# FOC_Driver.net
KiCad netlist of a schematic drawn in Altium Designer
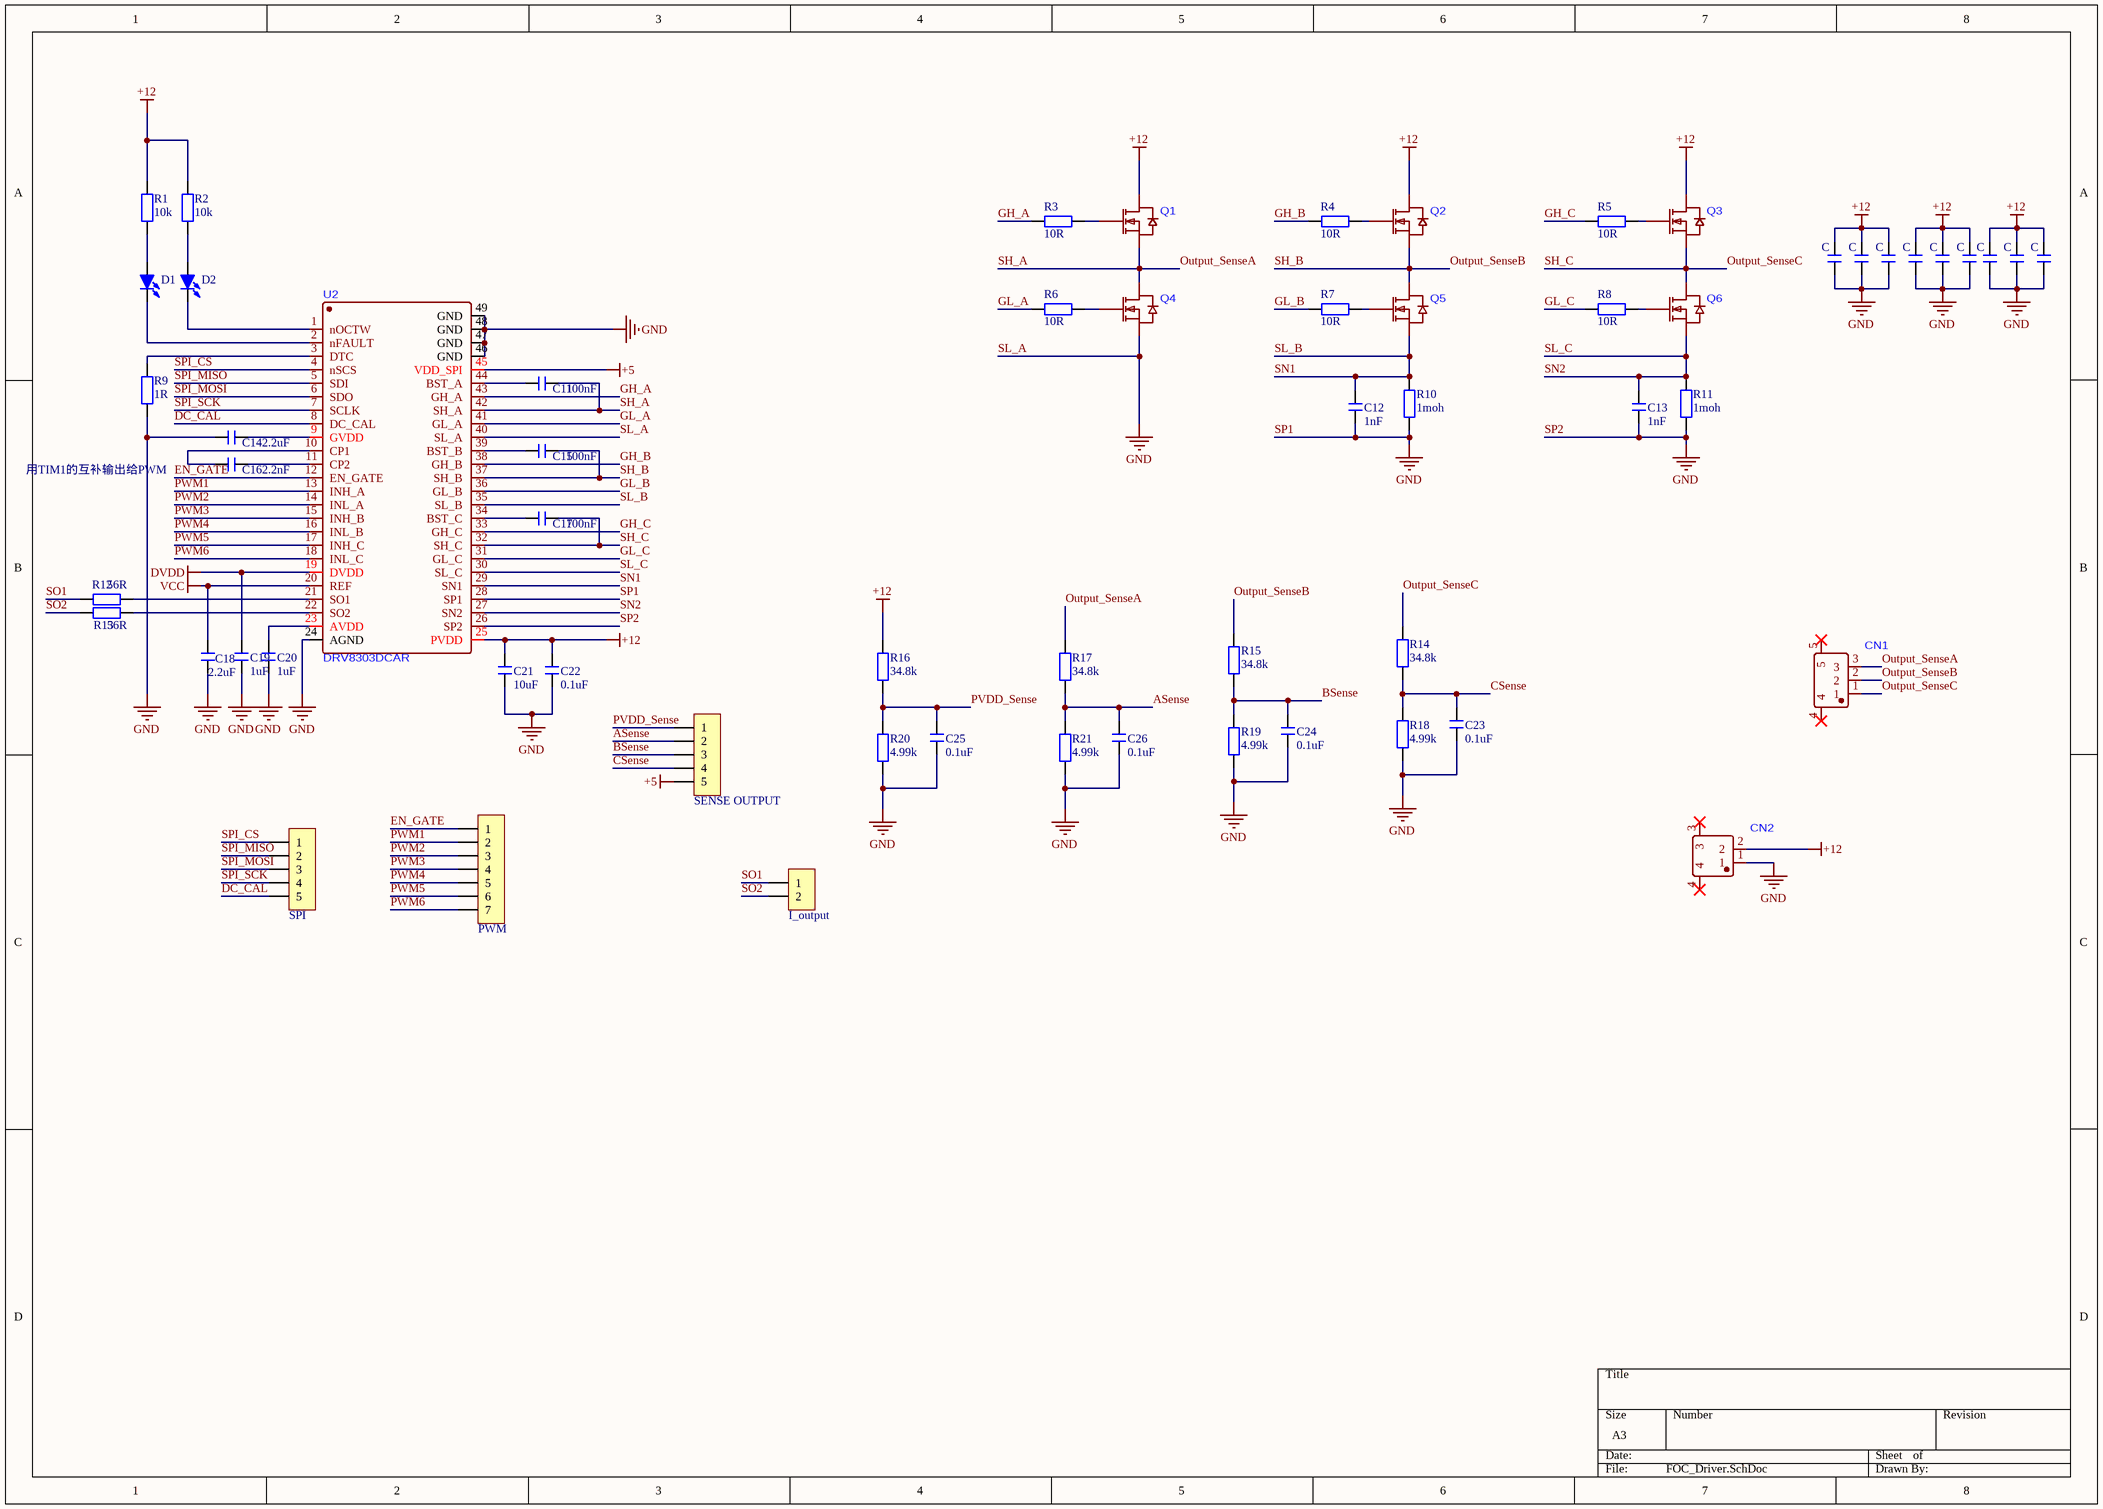
[diagram p0: FOC_Driver.SchDoc]

(export (version "E")
  (design (tool "Eeschema 10.0.6"))
  (components
    (comp (ref "C2")
      (value "C")
      (footprint "C 0805_M")
      (description "无极性贴片电容")
      (fields (field (name "版权归属") "电协硬件组"))
      (libsource (lib "3.1   - 电阻-电容-电感") (part "C"))
    )
    (comp (ref "C3")
      (value "C")
      (footprint "C 0805_M")
      (description "无极性贴片电容")
      (fields (field (name "版权归属") "电协硬件组"))
      (libsource (lib "3.1   - 电阻-电容-电感") (part "C"))
    )
    (comp (ref "C4")
      (value "C")
      (footprint "C 0805_M")
      (description "无极性贴片电容")
      (fields (field (name "版权归属") "电协硬件组"))
      (libsource (lib "3.1   - 电阻-电容-电感") (part "C"))
    )
    (comp (ref "C5")
      (value "C")
      (footprint "C 0805_M")
      (description "无极性贴片电容")
      (fields (field (name "版权归属") "电协硬件组"))
      (libsource (lib "3.1   - 电阻-电容-电感") (part "C"))
    )
    (comp (ref "C6")
      (value "C")
      (footprint "C 0805_M")
      (description "无极性贴片电容")
      (fields (field (name "版权归属") "电协硬件组"))
      (libsource (lib "3.1   - 电阻-电容-电感") (part "C"))
    )
    (comp (ref "C7")
      (value "C")
      (footprint "C 0805_M")
      (description "无极性贴片电容")
      (fields (field (name "版权归属") "电协硬件组"))
      (libsource (lib "3.1   - 电阻-电容-电感") (part "C"))
    )
    (comp (ref "C8")
      (value "C")
      (footprint "C 0805_M")
      (description "无极性贴片电容")
      (fields (field (name "版权归属") "电协硬件组"))
      (libsource (lib "3.1   - 电阻-电容-电感") (part "C"))
    )
    (comp (ref "C9")
      (value "C")
      (footprint "C 0805_M")
      (description "无极性贴片电容")
      (fields (field (name "版权归属") "电协硬件组"))
      (libsource (lib "3.1   - 电阻-电容-电感") (part "C"))
    )
    (comp (ref "C10")
      (value "C")
      (footprint "C 0805_M")
      (description "无极性贴片电容")
      (fields (field (name "版权归属") "电协硬件组"))
      (libsource (lib "3.1   - 电阻-电容-电感") (part "C"))
    )
    (comp (ref "C11")
      (value "100nF")
      (footprint "C 0603_M")
      (description "无极性贴片电容")
      (fields (field (name "版权归属") "电协硬件组"))
      (libsource (lib "3.1   - 电阻-电容-电感") (part "C"))
    )
    (comp (ref "C12")
      (value "1nF")
      (footprint "C 0603_M")
      (description "无极性贴片电容")
      (fields (field (name "版权归属") "电协硬件组"))
      (libsource (lib "3.1   - 电阻-电容-电感") (part "C"))
    )
    (comp (ref "C13")
      (value "1nF")
      (footprint "C 0603_M")
      (description "无极性贴片电容")
      (fields (field (name "版权归属") "电协硬件组"))
      (libsource (lib "3.1   - 电阻-电容-电感") (part "C"))
    )
    (comp (ref "C14")
      (value "2.2uF")
      (footprint "C 0603_M")
      (description "无极性贴片电容")
      (fields (field (name "版权归属") "电协硬件组"))
      (libsource (lib "3.1   - 电阻-电容-电感") (part "C"))
    )
    (comp (ref "C15")
      (value "100nF")
      (footprint "C 0603_M")
      (description "无极性贴片电容")
      (fields (field (name "版权归属") "电协硬件组"))
      (libsource (lib "3.1   - 电阻-电容-电感") (part "C"))
    )
    (comp (ref "C16")
      (value "2.2nF")
      (footprint "C 0603_M")
      (description "无极性贴片电容")
      (fields (field (name "版权归属") "电协硬件组"))
      (libsource (lib "3.1   - 电阻-电容-电感") (part "C"))
    )
    (comp (ref "C17")
      (value "100nF")
      (footprint "C 0603_M")
      (description "无极性贴片电容")
      (fields (field (name "版权归属") "电协硬件组"))
      (libsource (lib "3.1   - 电阻-电容-电感") (part "C"))
    )
    (comp (ref "C18")
      (value "2.2uF")
      (footprint "C 0603_M")
      (description "无极性贴片电容")
      (fields (field (name "版权归属") "电协硬件组"))
      (libsource (lib "3.1   - 电阻-电容-电感") (part "C"))
    )
    (comp (ref "C19")
      (value "1uF")
      (footprint "C 0603_M")
      (description "无极性贴片电容")
      (fields (field (name "版权归属") "电协硬件组"))
      (libsource (lib "3.1   - 电阻-电容-电感") (part "C"))
    )
    (comp (ref "C20")
      (value "1uF")
      (footprint "C 0603_M")
      (description "无极性贴片电容")
      (fields (field (name "版权归属") "电协硬件组"))
      (libsource (lib "3.1   - 电阻-电容-电感") (part "C"))
    )
    (comp (ref "C21")
      (value "10uF")
      (footprint "C 0603_M")
      (description "无极性贴片电容")
      (fields (field (name "版权归属") "电协硬件组"))
      (libsource (lib "3.1   - 电阻-电容-电感") (part "C"))
    )
    (comp (ref "C22")
      (value "0.1uF")
      (footprint "C 0603_M")
      (description "无极性贴片电容")
      (fields (field (name "版权归属") "电协硬件组"))
      (libsource (lib "3.1   - 电阻-电容-电感") (part "C"))
    )
    (comp (ref "C23")
      (value "0.1uF")
      (footprint "C 0603_M")
      (description "无极性贴片电容")
      (fields (field (name "版权归属") "电协硬件组"))
      (libsource (lib "3.1   - 电阻-电容-电感") (part "C"))
    )
    (comp (ref "C24")
      (value "0.1uF")
      (footprint "C 0603_M")
      (description "无极性贴片电容")
      (fields (field (name "版权归属") "电协硬件组"))
      (libsource (lib "3.1   - 电阻-电容-电感") (part "C"))
    )
    (comp (ref "C25")
      (value "0.1uF")
      (footprint "C 0603_M")
      (description "无极性贴片电容")
      (fields (field (name "版权归属") "电协硬件组"))
      (libsource (lib "3.1   - 电阻-电容-电感") (part "C"))
    )
    (comp (ref "C26")
      (value "0.1uF")
      (footprint "C 0603_M")
      (description "无极性贴片电容")
      (fields (field (name "版权归属") "电协硬件组"))
      (libsource (lib "3.1   - 电阻-电容-电感") (part "C"))
    )
    (comp (ref "CN1")
      (value "MR30PW-F")
      (footprint "CONN-TH_MR30PW-F")
      (libsource (lib "DRV8303") (part "MR30PW-F"))
    )
    (comp (ref "CN2")
      (value "XT30PW-M")
      (footprint "CONN-TH_XT30PW-M")
      (libsource (lib "主控") (part "XT30PW-M"))
    )
    (comp (ref "D1")
      (value "LED-SMD")
      (footprint "LED 0603G")
      (description "贴片LED")
      (fields (field (name "版权归属") "电协硬件组"))
      (libsource (lib "9.1   - LED") (part "LED-SMD"))
    )
    (comp (ref "D2")
      (value "LED-SMD")
      (footprint "LED 0603G")
      (description "贴片LED")
      (fields (field (name "版权归属") "电协硬件组"))
      (libsource (lib "9.1   - LED") (part "LED-SMD"))
    )
    (comp (ref "I_output")
      (value "HDR-1X2")
      (footprint "HDR2.54-LI-2P")
      (description "2P接插件")
      (fields (field (name "版权归属") "源创客"))
      (libsource (lib "4.5   - 接插件-脚距2.54") (part "Header 2"))
    )
    (comp (ref "PWM")
      (value "HDR-1X7")
      (footprint "HDR2.54-LI-7P")
      (description "7P接插件")
      (fields (field (name "版权归属") "源创客"))
      (libsource (lib "4.5   - 接插件-脚距2.54") (part "Header 7"))
    )
    (comp (ref "Q1")
      (value "IRLR7843TRPBF")
      (footprint "TO-252-2_L6.5-W6.1-P4.58-LS10.0-TR")
      (libsource (lib "驱动") (part "IRLR7843TRPBF"))
    )
    (comp (ref "Q2")
      (value "IRLR7843TRPBF")
      (footprint "TO-252-2_L6.5-W6.1-P4.58-LS10.0-TR")
      (libsource (lib "驱动") (part "IRLR7843TRPBF"))
    )
    (comp (ref "Q3")
      (value "IRLR7843TRPBF")
      (footprint "TO-252-2_L6.5-W6.1-P4.58-LS10.0-TR")
      (libsource (lib "驱动") (part "IRLR7843TRPBF"))
    )
    (comp (ref "Q4")
      (value "IRLR7843TRPBF")
      (footprint "TO-252-2_L6.5-W6.1-P4.58-LS10.0-TR")
      (libsource (lib "驱动") (part "IRLR7843TRPBF"))
    )
    (comp (ref "Q5")
      (value "IRLR7843TRPBF")
      (footprint "TO-252-2_L6.5-W6.1-P4.58-LS10.0-TR")
      (libsource (lib "驱动") (part "IRLR7843TRPBF"))
    )
    (comp (ref "Q6")
      (value "IRLR7843TRPBF")
      (footprint "TO-252-2_L6.5-W6.1-P4.58-LS10.0-TR")
      (libsource (lib "驱动") (part "IRLR7843TRPBF"))
    )
    (comp (ref "R1")
      (value "10k")
      (footprint "R 0603_M")
      (description "贴片电阻")
      (fields (field (name "Comment") "R") (field (name "版权归属") "电协硬件组"))
      (libsource (lib "3.1   - 电阻-电容-电感") (part "R"))
    )
    (comp (ref "R2")
      (value "10k")
      (footprint "R 0603_M")
      (description "贴片电阻")
      (fields (field (name "Comment") "R") (field (name "版权归属") "电协硬件组"))
      (libsource (lib "3.1   - 电阻-电容-电感") (part "R"))
    )
    (comp (ref "R3")
      (value "10R")
      (footprint "R 0603_M")
      (description "贴片电阻")
      (fields (field (name "Comment") "R") (field (name "版权归属") "电协硬件组"))
      (libsource (lib "3.1   - 电阻-电容-电感") (part "R"))
    )
    (comp (ref "R4")
      (value "10R")
      (footprint "R 0603_M")
      (description "贴片电阻")
      (fields (field (name "Comment") "R") (field (name "版权归属") "电协硬件组"))
      (libsource (lib "3.1   - 电阻-电容-电感") (part "R"))
    )
    (comp (ref "R5")
      (value "10R")
      (footprint "R 0603_M")
      (description "贴片电阻")
      (fields (field (name "Comment") "R") (field (name "版权归属") "电协硬件组"))
      (libsource (lib "3.1   - 电阻-电容-电感") (part "R"))
    )
    (comp (ref "R6")
      (value "10R")
      (footprint "R 0603_M")
      (description "贴片电阻")
      (fields (field (name "Comment") "R") (field (name "版权归属") "电协硬件组"))
      (libsource (lib "3.1   - 电阻-电容-电感") (part "R"))
    )
    (comp (ref "R7")
      (value "10R")
      (footprint "R 0603_M")
      (description "贴片电阻")
      (fields (field (name "Comment") "R") (field (name "版权归属") "电协硬件组"))
      (libsource (lib "3.1   - 电阻-电容-电感") (part "R"))
    )
    (comp (ref "R8")
      (value "10R")
      (footprint "R 0603_M")
      (description "贴片电阻")
      (fields (field (name "Comment") "R") (field (name "版权归属") "电协硬件组"))
      (libsource (lib "3.1   - 电阻-电容-电感") (part "R"))
    )
    (comp (ref "R9")
      (value "1R")
      (footprint "R 0603_M")
      (description "贴片电阻")
      (fields (field (name "Comment") "R") (field (name "版权归属") "电协硬件组"))
      (libsource (lib "3.1   - 电阻-电容-电感") (part "R"))
    )
    (comp (ref "R10")
      (value "1moh")
      (footprint "R 1206_M")
      (description "贴片电阻")
      (fields (field (name "Comment") "R") (field (name "版权归属") "电协硬件组"))
      (libsource (lib "3.1   - 电阻-电容-电感") (part "R"))
    )
    (comp (ref "R11")
      (value "1moh")
      (footprint "R 1206_M")
      (description "贴片电阻")
      (fields (field (name "Comment") "R") (field (name "版权归属") "电协硬件组"))
      (libsource (lib "3.1   - 电阻-电容-电感") (part "R"))
    )
    (comp (ref "R12")
      (value "56R")
      (footprint "R 0603_M")
      (description "贴片电阻")
      (fields (field (name "Comment") "R") (field (name "版权归属") "电协硬件组"))
      (libsource (lib "3.1   - 电阻-电容-电感") (part "R"))
    )
    (comp (ref "R13")
      (value "56R")
      (footprint "R 0603_M")
      (description "贴片电阻")
      (fields (field (name "Comment") "R") (field (name "版权归属") "电协硬件组"))
      (libsource (lib "3.1   - 电阻-电容-电感") (part "R"))
    )
    (comp (ref "R14")
      (value "34.8k")
      (footprint "R 0603_M")
      (description "贴片电阻")
      (fields (field (name "Comment") "R") (field (name "版权归属") "电协硬件组"))
      (libsource (lib "3.1   - 电阻-电容-电感") (part "R"))
    )
    (comp (ref "R15")
      (value "34.8k")
      (footprint "R 0603_M")
      (description "贴片电阻")
      (fields (field (name "Comment") "R") (field (name "版权归属") "电协硬件组"))
      (libsource (lib "3.1   - 电阻-电容-电感") (part "R"))
    )
    (comp (ref "R16")
      (value "34.8k")
      (footprint "R 0603_M")
      (description "贴片电阻")
      (fields (field (name "Comment") "R") (field (name "版权归属") "电协硬件组"))
      (libsource (lib "3.1   - 电阻-电容-电感") (part "R"))
    )
    (comp (ref "R17")
      (value "34.8k")
      (footprint "R 0603_M")
      (description "贴片电阻")
      (fields (field (name "Comment") "R") (field (name "版权归属") "电协硬件组"))
      (libsource (lib "3.1   - 电阻-电容-电感") (part "R"))
    )
    (comp (ref "R18")
      (value "4.99k")
      (footprint "R 0603_M")
      (description "贴片电阻")
      (fields (field (name "Comment") "R") (field (name "版权归属") "电协硬件组"))
      (libsource (lib "3.1   - 电阻-电容-电感") (part "R"))
    )
    (comp (ref "R19")
      (value "4.99k")
      (footprint "R 0603_M")
      (description "贴片电阻")
      (fields (field (name "Comment") "R") (field (name "版权归属") "电协硬件组"))
      (libsource (lib "3.1   - 电阻-电容-电感") (part "R"))
    )
    (comp (ref "R20")
      (value "4.99k")
      (footprint "R 0603_M")
      (description "贴片电阻")
      (fields (field (name "Comment") "R") (field (name "版权归属") "电协硬件组"))
      (libsource (lib "3.1   - 电阻-电容-电感") (part "R"))
    )
    (comp (ref "R21")
      (value "4.99k")
      (footprint "R 0603_M")
      (description "贴片电阻")
      (fields (field (name "Comment") "R") (field (name "版权归属") "电协硬件组"))
      (libsource (lib "3.1   - 电阻-电容-电感") (part "R"))
    )
    (comp (ref "SENSE OUTPUT")
      (value "HDR-1X5")
      (footprint "HDR2.54-LI-5P")
      (description "5P接插件")
      (fields (field (name "版权归属") "源创客"))
      (libsource (lib "4.5   - 接插件-脚距2.54") (part "Header 5"))
    )
    (comp (ref "SPI")
      (value "HDR-1X5")
      (footprint "HDR2.54-LI-5P")
      (description "5P接插件")
      (fields (field (name "版权归属") "源创客"))
      (libsource (lib "4.5   - 接插件-脚距2.54") (part "Header 5"))
    )
    (comp (ref "U2")
      (value "DRV8303DCAR")
      (footprint "HTSSOP-48_L12.5-W6.1-P0.50-LS8.1-BL-EP")
      (libsource (lib "DRV8303") (part "DRV8303DCAR"))
    )
  )
  (nets
    (net (code "1") (name "+5") (class "Default")
      (node (ref "SENSE OUTPUT") (pin "5") (pinfunction "5_5") (pintype "passive"))
      (node (ref "U2") (pin "45") (pinfunction "VDD_SPI_45") (pintype "passive"))
    )
    (net (code "2") (name "+12") (class "Default")
      (node (ref "C10") (pin "2") (pinfunction "2_2") (pintype "passive"))
      (node (ref "C2") (pin "2") (pinfunction "2_2") (pintype "passive"))
      (node (ref "C21") (pin "2") (pinfunction "2_2") (pintype "passive"))
      (node (ref "C22") (pin "2") (pinfunction "2_2") (pintype "passive"))
      (node (ref "C3") (pin "2") (pinfunction "2_2") (pintype "passive"))
      (node (ref "C4") (pin "2") (pinfunction "2_2") (pintype "passive"))
      (node (ref "C5") (pin "2") (pinfunction "2_2") (pintype "passive"))
      (node (ref "C6") (pin "2") (pinfunction "2_2") (pintype "passive"))
      (node (ref "C7") (pin "2") (pinfunction "2_2") (pintype "passive"))
      (node (ref "C8") (pin "2") (pinfunction "2_2") (pintype "passive"))
      (node (ref "C9") (pin "2") (pinfunction "2_2") (pintype "passive"))
      (node (ref "CN2") (pin "2") (pinfunction "2_2") (pintype "passive"))
      (node (ref "Q1") (pin "4") (pinfunction "D_4") (pintype "passive"))
      (node (ref "Q2") (pin "4") (pinfunction "D_4") (pintype "passive"))
      (node (ref "Q3") (pin "4") (pinfunction "D_4") (pintype "passive"))
      (node (ref "R1") (pin "2") (pinfunction "2_2") (pintype "passive"))
      (node (ref "R16") (pin "2") (pinfunction "2_2") (pintype "passive"))
      (node (ref "R2") (pin "2") (pinfunction "2_2") (pintype "passive"))
      (node (ref "U2") (pin "25") (pinfunction "PVDD_25") (pintype "passive"))
    )
    (net (code "3") (name "/ASense") (class "Default")
      (node (ref "C26") (pin "2") (pinfunction "2_2") (pintype "passive"))
      (node (ref "R17") (pin "1") (pinfunction "1_1") (pintype "passive"))
      (node (ref "R21") (pin "2") (pinfunction "2_2") (pintype "passive"))
      (node (ref "SENSE OUTPUT") (pin "2") (pinfunction "2_2") (pintype "passive"))
    )
    (net (code "4") (name "/BSense") (class "Default")
      (node (ref "C24") (pin "2") (pinfunction "2_2") (pintype "passive"))
      (node (ref "R15") (pin "1") (pinfunction "1_1") (pintype "passive"))
      (node (ref "R19") (pin "2") (pinfunction "2_2") (pintype "passive"))
      (node (ref "SENSE OUTPUT") (pin "3") (pinfunction "3_3") (pintype "passive"))
    )
    (net (code "5") (name "/CSense") (class "Default")
      (node (ref "C23") (pin "2") (pinfunction "2_2") (pintype "passive"))
      (node (ref "R14") (pin "1") (pinfunction "1_1") (pintype "passive"))
      (node (ref "R18") (pin "2") (pinfunction "2_2") (pintype "passive"))
      (node (ref "SENSE OUTPUT") (pin "4") (pinfunction "4_4") (pintype "passive"))
    )
    (net (code "6") (name "/DC_CAL") (class "Default")
      (node (ref "SPI") (pin "5") (pinfunction "5_5") (pintype "passive"))
      (node (ref "U2") (pin "8") (pinfunction "DC_CAL_8") (pintype "passive"))
    )
    (net (code "7") (name "/EN_GATE") (class "Default")
      (node (ref "PWM") (pin "1") (pinfunction "1_1") (pintype "passive"))
      (node (ref "U2") (pin "12") (pinfunction "EN_GATE_12") (pintype "passive"))
    )
    (net (code "8") (name "/GH_A") (class "Default")
      (node (ref "R3") (pin "2") (pinfunction "2_2") (pintype "passive"))
      (node (ref "U2") (pin "43") (pinfunction "GH_A_43") (pintype "passive"))
    )
    (net (code "9") (name "/GH_B") (class "Default")
      (node (ref "R4") (pin "2") (pinfunction "2_2") (pintype "passive"))
      (node (ref "U2") (pin "38") (pinfunction "GH_B_38") (pintype "passive"))
    )
    (net (code "10") (name "/GH_C") (class "Default")
      (node (ref "R5") (pin "2") (pinfunction "2_2") (pintype "passive"))
      (node (ref "U2") (pin "33") (pinfunction "GH_C_33") (pintype "passive"))
    )
    (net (code "11") (name "/GL_A") (class "Default")
      (node (ref "R6") (pin "2") (pinfunction "2_2") (pintype "passive"))
      (node (ref "U2") (pin "41") (pinfunction "GL_A_41") (pintype "passive"))
    )
    (net (code "12") (name "/GL_B") (class "Default")
      (node (ref "R7") (pin "2") (pinfunction "2_2") (pintype "passive"))
      (node (ref "U2") (pin "36") (pinfunction "GL_B_36") (pintype "passive"))
    )
    (net (code "13") (name "/GL_C") (class "Default")
      (node (ref "R8") (pin "2") (pinfunction "2_2") (pintype "passive"))
      (node (ref "U2") (pin "31") (pinfunction "GL_C_31") (pintype "passive"))
    )
    (net (code "14") (name "/Output_SenseA") (class "Default")
      (node (ref "C11") (pin "2") (pinfunction "2_2") (pintype "passive"))
      (node (ref "CN1") (pin "3") (pinfunction "3_3") (pintype "passive"))
      (node (ref "Q1") (pin "3") (pinfunction "S_3") (pintype "passive"))
      (node (ref "Q4") (pin "4") (pinfunction "D_4") (pintype "passive"))
      (node (ref "R17") (pin "2") (pinfunction "2_2") (pintype "passive"))
      (node (ref "U2") (pin "42") (pinfunction "SH_A_42") (pintype "passive"))
    )
    (net (code "15") (name "/Output_SenseB") (class "Default")
      (node (ref "C15") (pin "2") (pinfunction "2_2") (pintype "passive"))
      (node (ref "CN1") (pin "2") (pinfunction "2_2") (pintype "passive"))
      (node (ref "Q2") (pin "3") (pinfunction "S_3") (pintype "passive"))
      (node (ref "Q5") (pin "4") (pinfunction "D_4") (pintype "passive"))
      (node (ref "R15") (pin "2") (pinfunction "2_2") (pintype "passive"))
      (node (ref "U2") (pin "37") (pinfunction "SH_B_37") (pintype "passive"))
    )
    (net (code "16") (name "/Output_SenseC") (class "Default")
      (node (ref "C17") (pin "2") (pinfunction "2_2") (pintype "passive"))
      (node (ref "CN1") (pin "1") (pinfunction "1_1") (pintype "passive"))
      (node (ref "Q3") (pin "3") (pinfunction "S_3") (pintype "passive"))
      (node (ref "Q6") (pin "4") (pinfunction "D_4") (pintype "passive"))
      (node (ref "R14") (pin "2") (pinfunction "2_2") (pintype "passive"))
      (node (ref "U2") (pin "32") (pinfunction "SH_C_32") (pintype "passive"))
    )
    (net (code "17") (name "/PVDD_Sense") (class "Default")
      (node (ref "C25") (pin "2") (pinfunction "2_2") (pintype "passive"))
      (node (ref "R16") (pin "1") (pinfunction "1_1") (pintype "passive"))
      (node (ref "R20") (pin "2") (pinfunction "2_2") (pintype "passive"))
      (node (ref "SENSE OUTPUT") (pin "1") (pinfunction "1_1") (pintype "passive"))
    )
    (net (code "18") (name "/PWM1") (class "Default")
      (node (ref "PWM") (pin "2") (pinfunction "2_2") (pintype "passive"))
      (node (ref "U2") (pin "13") (pinfunction "INH_A_13") (pintype "passive"))
    )
    (net (code "19") (name "/PWM2") (class "Default")
      (node (ref "PWM") (pin "3") (pinfunction "3_3") (pintype "passive"))
      (node (ref "U2") (pin "14") (pinfunction "INL_A_14") (pintype "passive"))
    )
    (net (code "20") (name "/PWM3") (class "Default")
      (node (ref "PWM") (pin "4") (pinfunction "4_4") (pintype "passive"))
      (node (ref "U2") (pin "15") (pinfunction "INH_B_15") (pintype "passive"))
    )
    (net (code "21") (name "/PWM4") (class "Default")
      (node (ref "PWM") (pin "5") (pinfunction "5_5") (pintype "passive"))
      (node (ref "U2") (pin "16") (pinfunction "INL_B_16") (pintype "passive"))
    )
    (net (code "22") (name "/PWM5") (class "Default")
      (node (ref "PWM") (pin "6") (pinfunction "6_6") (pintype "passive"))
      (node (ref "U2") (pin "17") (pinfunction "INH_C_17") (pintype "passive"))
    )
    (net (code "23") (name "/PWM6") (class "Default")
      (node (ref "PWM") (pin "7") (pinfunction "7_7") (pintype "passive"))
      (node (ref "U2") (pin "18") (pinfunction "INL_C_18") (pintype "passive"))
    )
    (net (code "24") (name "/SL_B") (class "Default")
      (node (ref "C12") (pin "2") (pinfunction "2_2") (pintype "passive"))
      (node (ref "Q5") (pin "3") (pinfunction "S_3") (pintype "passive"))
      (node (ref "R10") (pin "2") (pinfunction "2_2") (pintype "passive"))
      (node (ref "U2") (pin "29") (pinfunction "SN1_29") (pintype "passive"))
      (node (ref "U2") (pin "35") (pinfunction "SL_B_35") (pintype "passive"))
    )
    (net (code "25") (name "/SL_C") (class "Default")
      (node (ref "C13") (pin "2") (pinfunction "2_2") (pintype "passive"))
      (node (ref "Q6") (pin "3") (pinfunction "S_3") (pintype "passive"))
      (node (ref "R11") (pin "2") (pinfunction "2_2") (pintype "passive"))
      (node (ref "U2") (pin "27") (pinfunction "SN2_27") (pintype "passive"))
      (node (ref "U2") (pin "30") (pinfunction "SL_C_30") (pintype "passive"))
    )
    (net (code "26") (name "/SO1") (class "Default")
      (node (ref "I_output") (pin "1") (pinfunction "1_1") (pintype "passive"))
      (node (ref "R12") (pin "2") (pinfunction "2_2") (pintype "passive"))
    )
    (net (code "27") (name "/SO2") (class "Default")
      (node (ref "I_output") (pin "2") (pinfunction "2_2") (pintype "passive"))
      (node (ref "R13") (pin "2") (pinfunction "2_2") (pintype "passive"))
    )
    (net (code "28") (name "/SPI_CS") (class "Default")
      (node (ref "SPI") (pin "1") (pinfunction "1_1") (pintype "passive"))
      (node (ref "U2") (pin "4") (pinfunction "nSCS_4") (pintype "passive"))
    )
    (net (code "29") (name "/SPI_MISO") (class "Default")
      (node (ref "SPI") (pin "2") (pinfunction "2_2") (pintype "passive"))
      (node (ref "U2") (pin "5") (pinfunction "SDI_5") (pintype "passive"))
    )
    (net (code "30") (name "/SPI_MOSI") (class "Default")
      (node (ref "SPI") (pin "3") (pinfunction "3_3") (pintype "passive"))
      (node (ref "U2") (pin "6") (pinfunction "SDO_6") (pintype "passive"))
    )
    (net (code "31") (name "/SPI_SCK") (class "Default")
      (node (ref "SPI") (pin "4") (pinfunction "4_4") (pintype "passive"))
      (node (ref "U2") (pin "7") (pinfunction "SCLK_7") (pintype "passive"))
    )
    (net (code "32") (name "DVDD") (class "Default")
      (node (ref "C19") (pin "2") (pinfunction "2_2") (pintype "passive"))
      (node (ref "U2") (pin "19") (pinfunction "DVDD_19") (pintype "passive"))
    )
    (net (code "33") (name "GND") (class "Default")
      (node (ref "C10") (pin "1") (pinfunction "1_1") (pintype "passive"))
      (node (ref "C12") (pin "1") (pinfunction "1_1") (pintype "passive"))
      (node (ref "C13") (pin "1") (pinfunction "1_1") (pintype "passive"))
      (node (ref "C14") (pin "1") (pinfunction "1_1") (pintype "passive"))
      (node (ref "C18") (pin "1") (pinfunction "1_1") (pintype "passive"))
      (node (ref "C19") (pin "1") (pinfunction "1_1") (pintype "passive"))
      (node (ref "C2") (pin "1") (pinfunction "1_1") (pintype "passive"))
      (node (ref "C20") (pin "1") (pinfunction "1_1") (pintype "passive"))
      (node (ref "C21") (pin "1") (pinfunction "1_1") (pintype "passive"))
      (node (ref "C22") (pin "1") (pinfunction "1_1") (pintype "passive"))
      (node (ref "C23") (pin "1") (pinfunction "1_1") (pintype "passive"))
      (node (ref "C24") (pin "1") (pinfunction "1_1") (pintype "passive"))
      (node (ref "C25") (pin "1") (pinfunction "1_1") (pintype "passive"))
      (node (ref "C26") (pin "1") (pinfunction "1_1") (pintype "passive"))
      (node (ref "C3") (pin "1") (pinfunction "1_1") (pintype "passive"))
      (node (ref "C4") (pin "1") (pinfunction "1_1") (pintype "passive"))
      (node (ref "C5") (pin "1") (pinfunction "1_1") (pintype "passive"))
      (node (ref "C6") (pin "1") (pinfunction "1_1") (pintype "passive"))
      (node (ref "C7") (pin "1") (pinfunction "1_1") (pintype "passive"))
      (node (ref "C8") (pin "1") (pinfunction "1_1") (pintype "passive"))
      (node (ref "C9") (pin "1") (pinfunction "1_1") (pintype "passive"))
      (node (ref "CN2") (pin "1") (pinfunction "1_1") (pintype "passive"))
      (node (ref "Q4") (pin "3") (pinfunction "S_3") (pintype "passive"))
      (node (ref "R10") (pin "1") (pinfunction "1_1") (pintype "passive"))
      (node (ref "R11") (pin "1") (pinfunction "1_1") (pintype "passive"))
      (node (ref "R18") (pin "1") (pinfunction "1_1") (pintype "passive"))
      (node (ref "R19") (pin "1") (pinfunction "1_1") (pintype "passive"))
      (node (ref "R20") (pin "1") (pinfunction "1_1") (pintype "passive"))
      (node (ref "R21") (pin "1") (pinfunction "1_1") (pintype "passive"))
      (node (ref "R9") (pin "1") (pinfunction "1_1") (pintype "passive"))
      (node (ref "U2") (pin "24") (pinfunction "AGND_24") (pintype "passive"))
      (node (ref "U2") (pin "26") (pinfunction "SP2_26") (pintype "passive"))
      (node (ref "U2") (pin "28") (pinfunction "SP1_28") (pintype "passive"))
      (node (ref "U2") (pin "40") (pinfunction "SL_A_40") (pintype "passive"))
      (node (ref "U2") (pin "46") (pinfunction "GND_46") (pintype "passive"))
      (node (ref "U2") (pin "47") (pinfunction "GND_47") (pintype "passive"))
      (node (ref "U2") (pin "48") (pinfunction "GND_48") (pintype "passive"))
      (node (ref "U2") (pin "49") (pinfunction "GND_49") (pintype "passive"))
    )
    (net (code "34") (name "Net-(D1-A)") (class "Default")
      (node (ref "D1") (pin "1") (pinfunction "A_1") (pintype "passive"))
      (node (ref "R1") (pin "1") (pinfunction "1_1") (pintype "passive"))
    )
    (net (code "35") (name "Net-(D1-K)") (class "Default")
      (node (ref "D1") (pin "2") (pinfunction "K_2") (pintype "passive"))
      (node (ref "U2") (pin "2") (pinfunction "nFAULT_2") (pintype "passive"))
    )
    (net (code "36") (name "Net-(D2-A)") (class "Default")
      (node (ref "D2") (pin "1") (pinfunction "A_1") (pintype "passive"))
      (node (ref "R2") (pin "1") (pinfunction "1_1") (pintype "passive"))
    )
    (net (code "37") (name "Net-(D2-K)") (class "Default")
      (node (ref "D2") (pin "2") (pinfunction "K_2") (pintype "passive"))
      (node (ref "U2") (pin "1") (pinfunction "nOCTW_1") (pintype "passive"))
    )
    (net (code "38") (name "Net-(Q1-G)") (class "Default")
      (node (ref "Q1") (pin "1") (pinfunction "G_1") (pintype "passive"))
      (node (ref "R3") (pin "1") (pinfunction "1_1") (pintype "passive"))
    )
    (net (code "39") (name "Net-(Q2-G)") (class "Default")
      (node (ref "Q2") (pin "1") (pinfunction "G_1") (pintype "passive"))
      (node (ref "R4") (pin "1") (pinfunction "1_1") (pintype "passive"))
    )
    (net (code "40") (name "Net-(Q3-G)") (class "Default")
      (node (ref "Q3") (pin "1") (pinfunction "G_1") (pintype "passive"))
      (node (ref "R5") (pin "1") (pinfunction "1_1") (pintype "passive"))
    )
    (net (code "41") (name "Net-(Q4-G)") (class "Default")
      (node (ref "Q4") (pin "1") (pinfunction "G_1") (pintype "passive"))
      (node (ref "R6") (pin "1") (pinfunction "1_1") (pintype "passive"))
    )
    (net (code "42") (name "Net-(Q5-G)") (class "Default")
      (node (ref "Q5") (pin "1") (pinfunction "G_1") (pintype "passive"))
      (node (ref "R7") (pin "1") (pinfunction "1_1") (pintype "passive"))
    )
    (net (code "43") (name "Net-(Q6-G)") (class "Default")
      (node (ref "Q6") (pin "1") (pinfunction "G_1") (pintype "passive"))
      (node (ref "R8") (pin "1") (pinfunction "1_1") (pintype "passive"))
    )
    (net (code "44") (name "Net-(U2-AVDD)") (class "Default")
      (node (ref "C20") (pin "2") (pinfunction "2_2") (pintype "passive"))
      (node (ref "U2") (pin "23") (pinfunction "AVDD_23") (pintype "passive"))
    )
    (net (code "45") (name "Net-(U2-BST_A)") (class "Default")
      (node (ref "C11") (pin "1") (pinfunction "1_1") (pintype "passive"))
      (node (ref "U2") (pin "44") (pinfunction "BST_A_44") (pintype "passive"))
    )
    (net (code "46") (name "Net-(U2-BST_B)") (class "Default")
      (node (ref "C15") (pin "1") (pinfunction "1_1") (pintype "passive"))
      (node (ref "U2") (pin "39") (pinfunction "BST_B_39") (pintype "passive"))
    )
    (net (code "47") (name "Net-(U2-BST_C)") (class "Default")
      (node (ref "C17") (pin "1") (pinfunction "1_1") (pintype "passive"))
      (node (ref "U2") (pin "34") (pinfunction "BST_C_34") (pintype "passive"))
    )
    (net (code "48") (name "Net-(U2-CP1)") (class "Default")
      (node (ref "C16") (pin "1") (pinfunction "1_1") (pintype "passive"))
      (node (ref "U2") (pin "10") (pinfunction "CP1_10") (pintype "passive"))
    )
    (net (code "49") (name "Net-(U2-CP2)") (class "Default")
      (node (ref "C16") (pin "2") (pinfunction "2_2") (pintype "passive"))
      (node (ref "U2") (pin "11") (pinfunction "CP2_11") (pintype "passive"))
    )
    (net (code "50") (name "Net-(U2-DTC)") (class "Default")
      (node (ref "R9") (pin "2") (pinfunction "2_2") (pintype "passive"))
      (node (ref "U2") (pin "3") (pinfunction "DTC_3") (pintype "passive"))
    )
    (net (code "51") (name "Net-(U2-GVDD)") (class "Default")
      (node (ref "C14") (pin "2") (pinfunction "2_2") (pintype "passive"))
      (node (ref "U2") (pin "9") (pinfunction "GVDD_9") (pintype "passive"))
    )
    (net (code "52") (name "Net-(U2-SO1)") (class "Default")
      (node (ref "R12") (pin "1") (pinfunction "1_1") (pintype "passive"))
      (node (ref "U2") (pin "21") (pinfunction "SO1_21") (pintype "passive"))
    )
    (net (code "53") (name "Net-(U2-SO2)") (class "Default")
      (node (ref "R13") (pin "1") (pinfunction "1_1") (pintype "passive"))
      (node (ref "U2") (pin "22") (pinfunction "SO2_22") (pintype "passive"))
    )
    (net (code "54") (name "VCC") (class "Default")
      (node (ref "C18") (pin "2") (pinfunction "2_2") (pintype "passive"))
      (node (ref "U2") (pin "20") (pinfunction "REF_20") (pintype "passive"))
    )
    (net (code "55") (name "unconnected-(CN1-Pad4)") (class "Default")
      (node (ref "CN1") (pin "4") (pinfunction "4_4") (pintype "passive+no_connect"))
    )
    (net (code "56") (name "unconnected-(CN1-Pad5)") (class "Default")
      (node (ref "CN1") (pin "5") (pinfunction "5_5") (pintype "passive+no_connect"))
    )
    (net (code "57") (name "unconnected-(CN2-Pad3)") (class "Default")
      (node (ref "CN2") (pin "3") (pinfunction "3_3") (pintype "passive+no_connect"))
    )
    (net (code "58") (name "unconnected-(CN2-Pad4)") (class "Default")
      (node (ref "CN2") (pin "4") (pinfunction "4_4") (pintype "passive+no_connect"))
    )
  )
)
